# controller-left.net
KiCad netlist of a schematic drawn in EAGLE
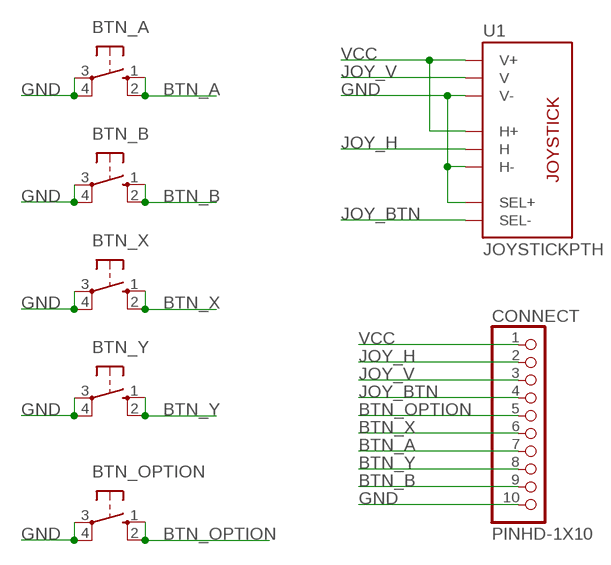
[diagram p0: schematic, sheet 1]

(export (version "E")
  (design (tool "Eeschema 10.0.6"))
  (components
    (comp (ref "BTN_A")
      (value "40-XX-ROUND")
      (footprint "eagle-import:B3F-40XX-ROUND")
      (libsource (lib "eagle-import") (part "40-XX-ROUND"))
    )
    (comp (ref "BTN_B")
      (value "40-XX-ROUND")
      (footprint "eagle-import:B3F-40XX-ROUND")
      (libsource (lib "eagle-import") (part "40-XX-ROUND"))
    )
    (comp (ref "BTN_OPTION")
      (value "40-XX-ROUND")
      (footprint "eagle-import:B3F-40XX-ROUND")
      (libsource (lib "eagle-import") (part "40-XX-ROUND"))
    )
    (comp (ref "BTN_X")
      (value "40-XX-ROUND")
      (footprint "eagle-import:B3F-40XX-ROUND")
      (libsource (lib "eagle-import") (part "40-XX-ROUND"))
    )
    (comp (ref "BTN_Y")
      (value "40-XX-ROUND")
      (footprint "eagle-import:B3F-40XX-ROUND")
      (libsource (lib "eagle-import") (part "40-XX-ROUND"))
    )
    (comp (ref "CONNECT")
      (value "PINHD-1X10")
      (footprint "eagle-import:1X10-BIG")
      (libsource (lib "eagle-import") (part "PINHD-1X10"))
    )
    (comp (ref "U1")
      (value "JOYSTICKPTH")
      (footprint "eagle-import:JOYSTICK")
      (libsource (lib "eagle-import") (part "JOYSTICKPTH"))
    )
  )
  (nets
    (net (code "1") (name "/BTN_A") (class "Default")
      (node (ref "BTN_A") (pin "1") (pinfunction "S_1") (pintype "passive"))
      (node (ref "BTN_A") (pin "2") (pinfunction "S1_2") (pintype "passive"))
      (node (ref "CONNECT") (pin "7") (pinfunction "7_7") (pintype "passive"))
    )
    (net (code "2") (name "/BTN_B") (class "Default")
      (node (ref "BTN_B") (pin "1") (pinfunction "S_1") (pintype "passive"))
      (node (ref "BTN_B") (pin "2") (pinfunction "S1_2") (pintype "passive"))
      (node (ref "CONNECT") (pin "9") (pinfunction "9_9") (pintype "passive"))
    )
    (net (code "3") (name "/BTN_OPTION") (class "Default")
      (node (ref "BTN_OPTION") (pin "1") (pinfunction "S_1") (pintype "passive"))
      (node (ref "BTN_OPTION") (pin "2") (pinfunction "S1_2") (pintype "passive"))
      (node (ref "CONNECT") (pin "5") (pinfunction "5_5") (pintype "passive"))
    )
    (net (code "4") (name "/BTN_X") (class "Default")
      (node (ref "BTN_X") (pin "1") (pinfunction "S_1") (pintype "passive"))
      (node (ref "BTN_X") (pin "2") (pinfunction "S1_2") (pintype "passive"))
      (node (ref "CONNECT") (pin "6") (pinfunction "6_6") (pintype "passive"))
    )
    (net (code "5") (name "/BTN_Y") (class "Default")
      (node (ref "BTN_Y") (pin "1") (pinfunction "S_1") (pintype "passive"))
      (node (ref "BTN_Y") (pin "2") (pinfunction "S1_2") (pintype "passive"))
      (node (ref "CONNECT") (pin "8") (pinfunction "8_8") (pintype "passive"))
    )
    (net (code "6") (name "/GND") (class "Default")
      (node (ref "BTN_A") (pin "3") (pinfunction "P_3") (pintype "passive"))
      (node (ref "BTN_A") (pin "4") (pinfunction "P1_4") (pintype "passive"))
      (node (ref "BTN_B") (pin "3") (pinfunction "P_3") (pintype "passive"))
      (node (ref "BTN_B") (pin "4") (pinfunction "P1_4") (pintype "passive"))
      (node (ref "BTN_OPTION") (pin "3") (pinfunction "P_3") (pintype "passive"))
      (node (ref "BTN_OPTION") (pin "4") (pinfunction "P1_4") (pintype "passive"))
      (node (ref "BTN_X") (pin "3") (pinfunction "P_3") (pintype "passive"))
      (node (ref "BTN_X") (pin "4") (pinfunction "P1_4") (pintype "passive"))
      (node (ref "BTN_Y") (pin "3") (pinfunction "P_3") (pintype "passive"))
      (node (ref "BTN_Y") (pin "4") (pinfunction "P1_4") (pintype "passive"))
      (node (ref "CONNECT") (pin "10") (pinfunction "10_10") (pintype "passive"))
      (node (ref "U1") (pin "B1A") (pinfunction "SEL+_B1A") (pintype "bidirectional"))
      (node (ref "U1") (pin "H3") (pinfunction "H-_H3") (pintype "bidirectional"))
      (node (ref "U1") (pin "V3") (pinfunction "V-_V3") (pintype "bidirectional"))
    )
    (net (code "7") (name "/JOY_BTN") (class "Default")
      (node (ref "CONNECT") (pin "4") (pinfunction "4_4") (pintype "passive"))
      (node (ref "U1") (pin "B2A") (pinfunction "SEL-_B2A") (pintype "bidirectional"))
    )
    (net (code "8") (name "/JOY_H") (class "Default")
      (node (ref "CONNECT") (pin "2") (pinfunction "2_2") (pintype "passive"))
      (node (ref "U1") (pin "H2") (pinfunction "H_H2") (pintype "bidirectional"))
    )
    (net (code "9") (name "/JOY_V") (class "Default")
      (node (ref "CONNECT") (pin "3") (pinfunction "3_3") (pintype "passive"))
      (node (ref "U1") (pin "V2") (pinfunction "V_V2") (pintype "bidirectional"))
    )
    (net (code "10") (name "/VCC") (class "Default")
      (node (ref "CONNECT") (pin "1") (pinfunction "1_1") (pintype "passive"))
      (node (ref "U1") (pin "H1") (pinfunction "H+_H1") (pintype "bidirectional"))
      (node (ref "U1") (pin "V1") (pinfunction "V+_V1") (pintype "bidirectional"))
    )
  )
)
